# Z-ONE.net
KiCad netlist of a schematic drawn in EAGLE
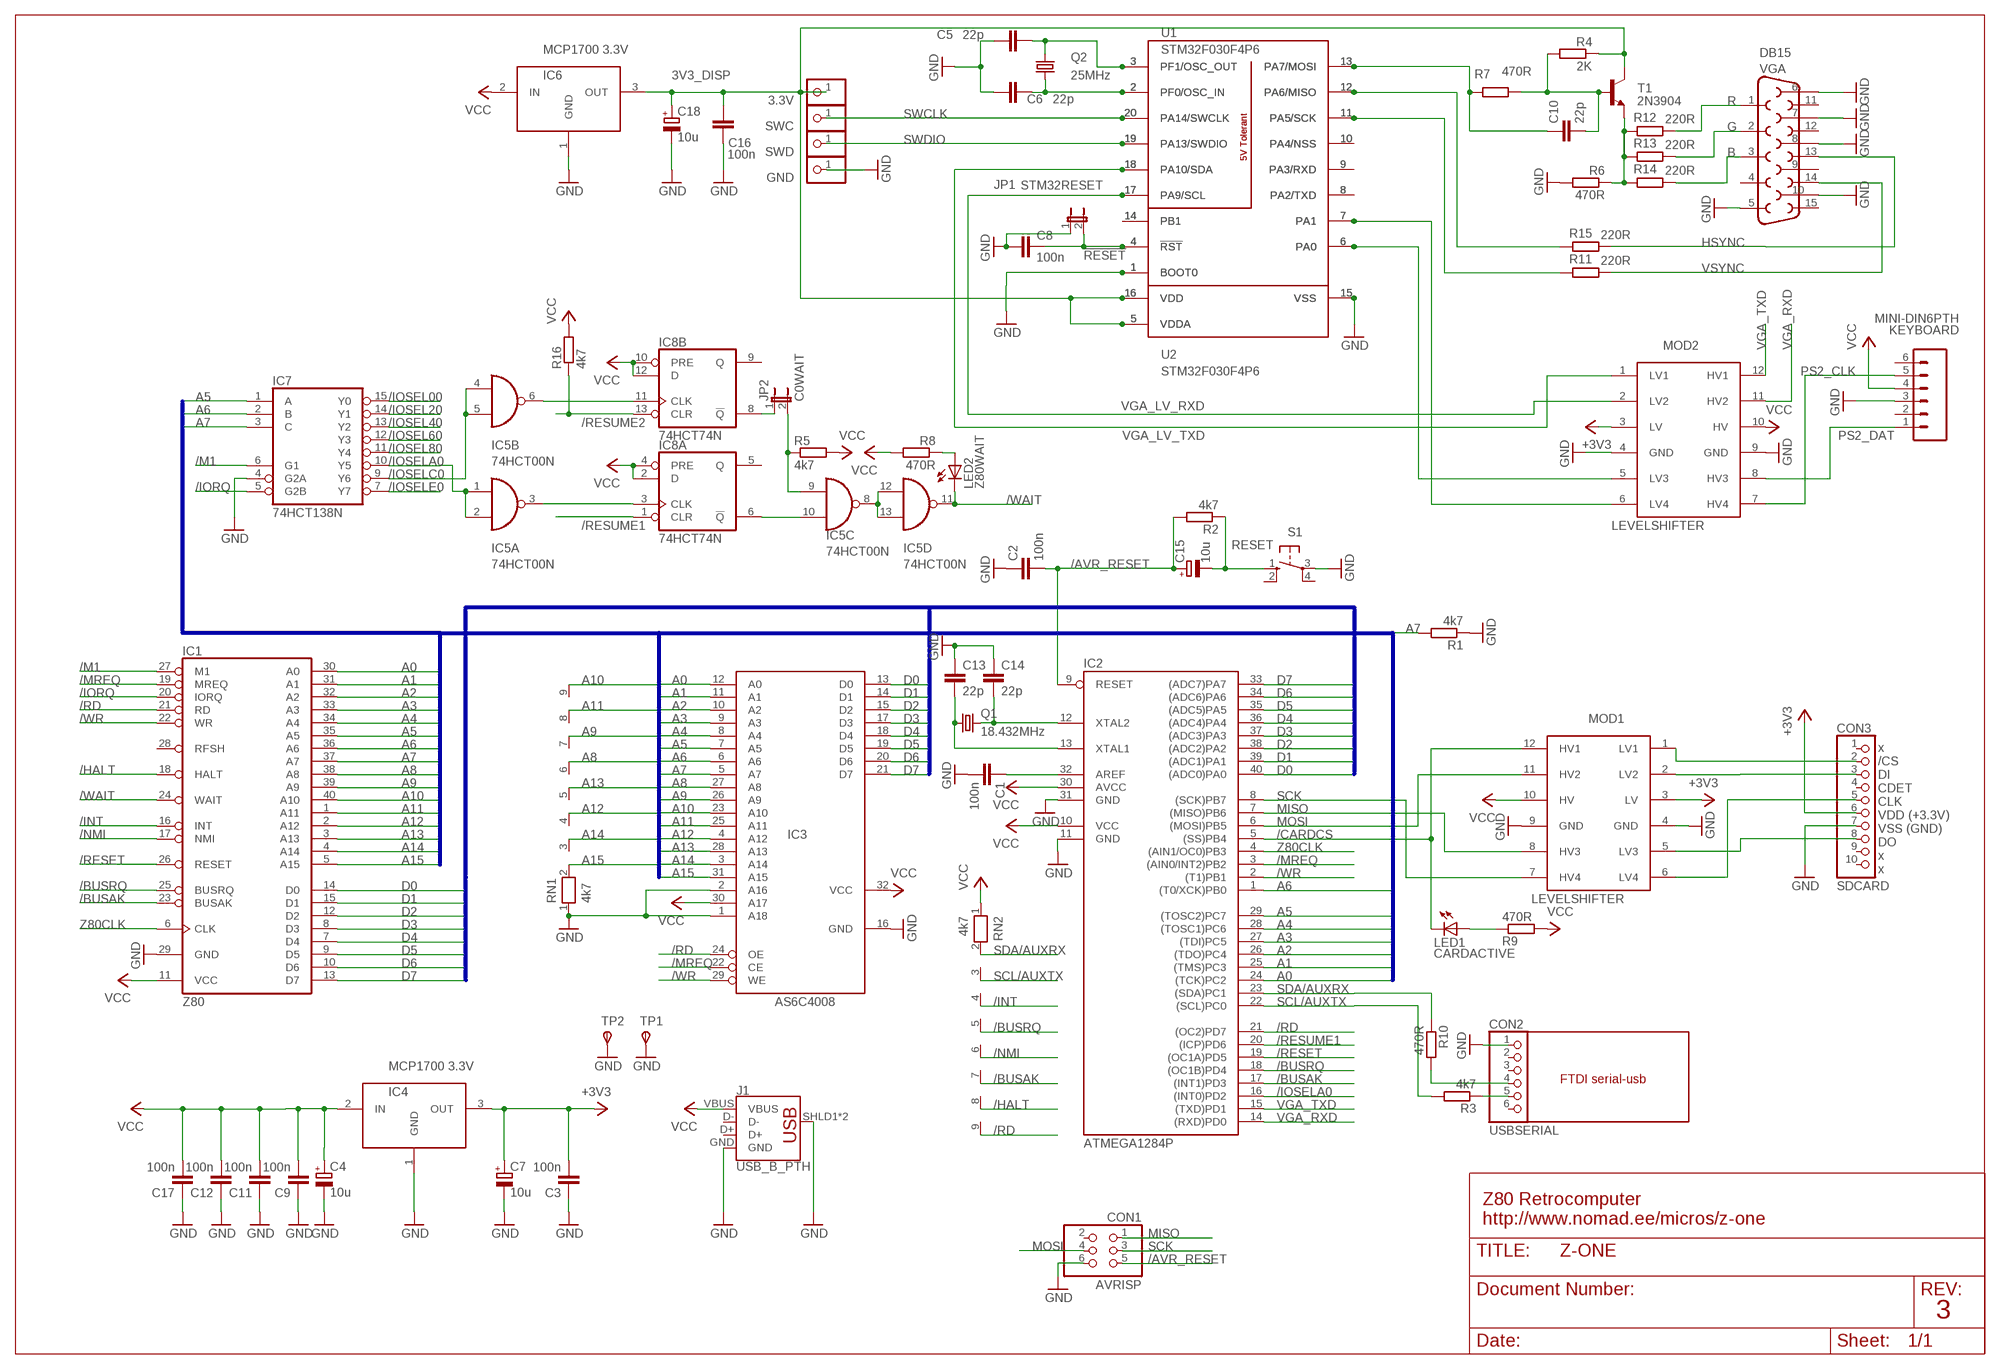
[diagram p0: schematic, sheet 1]

(export (version "E")
  (design (tool "Eeschema 10.0.6"))
  (components
    (comp (ref "3.3V")
      (value "PINHD-1X1")
      (footprint "eagle-import:1X01")
      (libsource (lib "eagle-import") (part "PINHD-1X1"))
    )
    (comp (ref "C1")
      (value "100n")
      (footprint "eagle-import:C025-025X050")
      (fields (field (name "PARTNO") "0.1UF, 0603"))
      (libsource (lib "eagle-import") (part "C-EU025-025X050"))
    )
    (comp (ref "C2")
      (value "100n")
      (footprint "eagle-import:C025-025X050")
      (fields (field (name "PARTNO") "0.1UF, 0603"))
      (libsource (lib "eagle-import") (part "C-EU025-025X050"))
    )
    (comp (ref "C3")
      (value "100n")
      (footprint "eagle-import:C025-025X050")
      (fields (field (name "PARTNO") "0.1UF, 0603"))
      (libsource (lib "eagle-import") (part "C-EU025-025X050"))
    )
    (comp (ref "C4")
      (value "10u")
      (footprint "eagle-import:E2,5-5")
      (libsource (lib "eagle-import") (part "CPOL-EUE2.5-5"))
    )
    (comp (ref "C5")
      (value "22p")
      (footprint "eagle-import:C025-025X050")
      (fields (field (name "PARTNO") "22PF, 0603"))
      (libsource (lib "eagle-import") (part "C-EU025-025X050"))
    )
    (comp (ref "C6")
      (value "22p")
      (footprint "eagle-import:C025-025X050")
      (fields (field (name "PARTNO") "22PF, 0603"))
      (libsource (lib "eagle-import") (part "C-EU025-025X050"))
    )
    (comp (ref "C7")
      (value "10u")
      (footprint "eagle-import:E2,5-5")
      (libsource (lib "eagle-import") (part "CPOL-EUE2.5-5"))
    )
    (comp (ref "C8")
      (value "100n")
      (footprint "eagle-import:C025-025X050")
      (fields (field (name "PARTNO") "0.1UF, 0603"))
      (libsource (lib "eagle-import") (part "C-EU025-025X050"))
    )
    (comp (ref "C9")
      (value "100n")
      (footprint "eagle-import:C025-025X050")
      (fields (field (name "PARTNO") "0.1UF, 0603"))
      (libsource (lib "eagle-import") (part "C-EU025-025X050"))
    )
    (comp (ref "C10")
      (value "22p")
      (footprint "eagle-import:C025-025X050")
      (fields (field (name "PARTNO") "22PF, 0603"))
      (libsource (lib "eagle-import") (part "C-EU025-025X050"))
    )
    (comp (ref "C11")
      (value "100n")
      (footprint "eagle-import:C025-025X050")
      (fields (field (name "PARTNO") "0.1UF, 0603"))
      (libsource (lib "eagle-import") (part "C-EU025-025X050"))
    )
    (comp (ref "C12")
      (value "100n")
      (footprint "eagle-import:C025-025X050")
      (fields (field (name "PARTNO") "0.1UF, 0603"))
      (libsource (lib "eagle-import") (part "C-EU025-025X050"))
    )
    (comp (ref "C13")
      (value "22p")
      (footprint "eagle-import:C025-025X050")
      (fields (field (name "PARTNO") "0.1UF, 0603"))
      (libsource (lib "eagle-import") (part "C-EU025-025X050"))
    )
    (comp (ref "C14")
      (value "22p")
      (footprint "eagle-import:C025-025X050")
      (fields (field (name "PARTNO") "0.1UF, 0603"))
      (libsource (lib "eagle-import") (part "C-EU025-025X050"))
    )
    (comp (ref "C15")
      (value "10u")
      (footprint "eagle-import:E2,5-5")
      (libsource (lib "eagle-import") (part "CPOL-EUE2.5-5"))
    )
    (comp (ref "C16")
      (value "100n")
      (footprint "eagle-import:C025-025X050")
      (fields (field (name "PARTNO") "0.1UF, 0603"))
      (libsource (lib "eagle-import") (part "C-EU025-025X050"))
    )
    (comp (ref "C17")
      (value "100n")
      (footprint "eagle-import:C025-025X050")
      (fields (field (name "PARTNO") "0.1UF, 0603"))
      (libsource (lib "eagle-import") (part "C-EU025-025X050"))
    )
    (comp (ref "C18")
      (value "10u")
      (footprint "eagle-import:E2,5-5")
      (libsource (lib "eagle-import") (part "CPOL-EUE2.5-5"))
    )
    (comp (ref "CON1")
      (value "AVRISP")
      (footprint "eagle-import:2X03")
      (libsource (lib "eagle-import") (part "PINHD-2X3"))
    )
    (comp (ref "CON2")
      (value "USBSERIAL")
      (footprint "eagle-import:1X06")
      (libsource (lib "eagle-import") (part "PINHD-1X6"))
    )
    (comp (ref "CON3")
      (value "SDCARD")
      (footprint "eagle-import:1X10")
      (libsource (lib "eagle-import") (part "PINHD-1X10"))
    )
    (comp (ref "GND")
      (value "PINHD-1X1")
      (footprint "eagle-import:1X01")
      (libsource (lib "eagle-import") (part "PINHD-1X1"))
    )
    (comp (ref "IC1")
      (value "Z80")
      (footprint "eagle-import:DIL40")
      (libsource (lib "eagle-import") (part "Z80CPU"))
    )
    (comp (ref "IC2")
      (value "ATMEGA1284P")
      (footprint "eagle-import:DIL40")
      (fields (field (name "MPN") "ATMEGA32-16PU"))
      (libsource (lib "eagle-import") (part "MEGA32-P"))
    )
    (comp (ref "IC3")
      (value "AS6C4008")
      (footprint "eagle-import:DIP32")
      (libsource (lib "eagle-import") (part "AS6C4008DIP32"))
    )
    (comp (ref "IC4")
      (value "MCP1700 3.3V")
      (footprint "eagle-import:TO-92")
      (libsource (lib "eagle-import") (part "MCP1700TO92"))
    )
    (comp (ref "IC5")
      (value "74HCT00N")
      (footprint "eagle-import:DIL14")
      (libsource (lib "eagle-import") (part "7400NHCT"))
    )
    (comp (ref "IC6")
      (value "MCP1700 3.3V")
      (footprint "eagle-import:TO-92")
      (libsource (lib "eagle-import") (part "MCP1700TO92"))
    )
    (comp (ref "IC7")
      (value "74HCT138N")
      (footprint "eagle-import:DIL16")
      (libsource (lib "eagle-import") (part "74138NHCT"))
    )
    (comp (ref "IC8")
      (value "74HCT74N")
      (footprint "eagle-import:DIL14")
      (libsource (lib "eagle-import") (part "7474NHCT"))
    )
    (comp (ref "J1")
      (value "USB_B_PTH")
      (footprint "eagle-import:USB-B-PTH")
      (libsource (lib "eagle-import") (part "USB_B_PTH"))
    )
    (comp (ref "JP1")
      (value "STM32RESET")
      (footprint "eagle-import:1X02")
      (libsource (lib "eagle-import") (part "JUMPER-2PTH"))
    )
    (comp (ref "JP2")
      (value "C0WAIT")
      (footprint "eagle-import:1X02")
      (libsource (lib "eagle-import") (part "JUMPER-2PTH"))
    )
    (comp (ref "KEYBOARD")
      (value "MINI-DIN6PTH")
      (footprint "eagle-import:MINI-DIN6")
      (libsource (lib "eagle-import") (part "MINI-DIN6PTH"))
    )
    (comp (ref "LED1")
      (value "CARDACTIVE")
      (footprint "eagle-import:LED3MM")
      (libsource (lib "eagle-import") (part "LED3MM"))
    )
    (comp (ref "LED2")
      (value "Z80WAIT")
      (footprint "eagle-import:LED3MM")
      (libsource (lib "eagle-import") (part "LED3MM"))
    )
    (comp (ref "MOD1")
      (value "LEVELSHIFTER")
      (footprint "eagle-import:LAVELSHIFTER_N")
      (libsource (lib "eagle-import") (part "LEVELSHIFTERNARROW"))
    )
    (comp (ref "MOD2")
      (value "LEVELSHIFTER")
      (footprint "eagle-import:LAVELSHIFTER_N")
      (libsource (lib "eagle-import") (part "LEVELSHIFTERNARROW"))
    )
    (comp (ref "Q1")
      (value "18.432MHz")
      (footprint "eagle-import:HC49_S")
      (libsource (lib "eagle-import") (part "CRYSTALHC49S"))
    )
    (comp (ref "Q2")
      (value "25MHz")
      (footprint "eagle-import:HC49_S")
      (libsource (lib "eagle-import") (part "CRYSTALHC49S"))
    )
    (comp (ref "R1")
      (value "4k7")
      (footprint "eagle-import:0204_7")
      (libsource (lib "eagle-import") (part "R-EU_0204/7"))
    )
    (comp (ref "R2")
      (value "4k7")
      (footprint "eagle-import:0204_7")
      (libsource (lib "eagle-import") (part "R-EU_0204/7"))
    )
    (comp (ref "R3")
      (value "4k7")
      (footprint "eagle-import:0204_7")
      (libsource (lib "eagle-import") (part "R-EU_0204/7"))
    )
    (comp (ref "R4")
      (value "2K")
      (footprint "eagle-import:0204_7")
      (fields (field (name "PARTNO") "2K, 0603"))
      (libsource (lib "eagle-import") (part "resistor_R-EU_0204/7"))
    )
    (comp (ref "R5")
      (value "4k7")
      (footprint "eagle-import:0204_7")
      (libsource (lib "eagle-import") (part "R-EU_0204/7"))
    )
    (comp (ref "R6")
      (value "470R")
      (footprint "eagle-import:0204_7")
      (fields (field (name "PARTNO") "475R, 0603"))
      (libsource (lib "eagle-import") (part "resistor_R-EU_0204/7"))
    )
    (comp (ref "R7")
      (value "470R")
      (footprint "eagle-import:0204_7")
      (fields (field (name "PARTNO") "475R, 0603"))
      (libsource (lib "eagle-import") (part "resistor_R-EU_0204/7"))
    )
    (comp (ref "R8")
      (value "470R")
      (footprint "eagle-import:0204_7")
      (fields (field (name "PARTNO") "475R, 0603"))
      (libsource (lib "eagle-import") (part "resistor_R-EU_0204/7"))
    )
    (comp (ref "R9")
      (value "470R")
      (footprint "eagle-import:0204_7")
      (fields (field (name "PARTNO") "475R, 0603"))
      (libsource (lib "eagle-import") (part "resistor_R-EU_0204/7"))
    )
    (comp (ref "R10")
      (value "470R")
      (footprint "eagle-import:0204_7")
      (libsource (lib "eagle-import") (part "R-EU_0204/7"))
    )
    (comp (ref "R11")
      (value "220R")
      (footprint "eagle-import:0204_7")
      (libsource (lib "eagle-import") (part "resistor_R-EU_0204/7"))
    )
    (comp (ref "R12")
      (value "220R")
      (footprint "eagle-import:0204_7")
      (libsource (lib "eagle-import") (part "resistor_R-EU_0204/7"))
    )
    (comp (ref "R13")
      (value "220R")
      (footprint "eagle-import:0204_7")
      (libsource (lib "eagle-import") (part "resistor_R-EU_0204/7"))
    )
    (comp (ref "R14")
      (value "220R")
      (footprint "eagle-import:0204_7")
      (libsource (lib "eagle-import") (part "resistor_R-EU_0204/7"))
    )
    (comp (ref "R15")
      (value "220R")
      (footprint "eagle-import:0204_7")
      (libsource (lib "eagle-import") (part "resistor_R-EU_0204/7"))
    )
    (comp (ref "R16")
      (value "4k7")
      (footprint "eagle-import:0204_7")
      (libsource (lib "eagle-import") (part "R-EU_0204/7"))
    )
    (comp (ref "RN1")
      (value "4k7")
      (footprint "eagle-import:RN-9")
      (libsource (lib "eagle-import") (part "RN08"))
    )
    (comp (ref "RN2")
      (value "4k7")
      (footprint "eagle-import:RN-9")
      (libsource (lib "eagle-import") (part "RN08"))
    )
    (comp (ref "S1")
      (value "RESET")
      (footprint "eagle-import:B3F-10XX")
      (fields (field (name "MPN") "B3F-1000"))
      (libsource (lib "eagle-import") (part "10-XX"))
    )
    (comp (ref "SWC")
      (value "PINHD-1X1")
      (footprint "eagle-import:1X01")
      (libsource (lib "eagle-import") (part "PINHD-1X1"))
    )
    (comp (ref "SWD")
      (value "PINHD-1X1")
      (footprint "eagle-import:1X01")
      (libsource (lib "eagle-import") (part "PINHD-1X1"))
    )
    (comp (ref "T1")
      (value "2N3904")
      (footprint "eagle-import:TO92")
      (libsource (lib "eagle-import") (part "2N3904"))
    )
    (comp (ref "TP1")
      (value "GND")
      (footprint "eagle-import:P1-13")
      (libsource (lib "eagle-import") (part "TPSPAD1-13"))
    )
    (comp (ref "TP2")
      (value "GND")
      (footprint "eagle-import:P1-13")
      (libsource (lib "eagle-import") (part "TPSPAD1-13"))
    )
    (comp (ref "U1")
      (value "STM32F030F4P6")
      (footprint "eagle-import:DIL20WIDE")
      (libsource (lib "eagle-import") (part "MISC-PROCESSOR_STM32F030F4P6DIL20MODULE"))
    )
    (comp (ref "U2")
      (value "STM32F030F4P6")
      (footprint "eagle-import:MISC-PROCESSOR_TSSOP20")
      (libsource (lib "eagle-import") (part "MISC-PROCESSOR_STM32F030F4P6"))
    )
    (comp (ref "VGA")
      (value "DB15")
      (footprint "eagle-import:DB15")
      (libsource (lib "eagle-import") (part "DB15"))
    )
  )
  (nets
    (net (code "1") (name "+3V3") (class "Default")
      (node (ref "C3") (pin "2") (pinfunction "2_2") (pintype "passive"))
      (node (ref "C7") (pin "+") (pinfunction "+_+") (pintype "passive"))
      (node (ref "CON3") (pin "6") (pinfunction "6_6") (pintype "passive"))
      (node (ref "IC4") (pin "3") (pinfunction "OUT_3") (pintype "bidirectional"))
      (node (ref "MOD1") (pin "3") (pinfunction "LV_3") (pintype "bidirectional"))
      (node (ref "MOD2") (pin "3") (pinfunction "LV_3") (pintype "bidirectional"))
    )
    (net (code "2") (name "/3V3_DISP") (class "Default")
      (node (ref "3.3V") (pin "1") (pinfunction "1_1") (pintype "passive"))
      (node (ref "C16") (pin "1") (pinfunction "1_1") (pintype "passive"))
      (node (ref "C18") (pin "+") (pinfunction "+_+") (pintype "passive"))
      (node (ref "IC6") (pin "3") (pinfunction "OUT_3") (pintype "bidirectional"))
      (node (ref "R4") (pin "1") (pinfunction "1_1") (pintype "passive"))
      (node (ref "T1") (pin "1") (pinfunction "C_1") (pintype "passive"))
      (node (ref "U1") (pin "16") (pinfunction "VDD_16") (pintype "input"))
      (node (ref "U1") (pin "5") (pinfunction "VDDA_5") (pintype "input"))
      (node (ref "U2") (pin "16") (pinfunction "VDD_16") (pintype "input"))
      (node (ref "U2") (pin "5") (pinfunction "VDDA_5") (pintype "input"))
    )
    (net (code "3") (name "/A0") (class "Default")
      (node (ref "IC1") (pin "30") (pinfunction "A0_30") (pintype "output"))
      (node (ref "IC2") (pin "24") (pinfunction "(TCK)PC2_24") (pintype "bidirectional"))
      (node (ref "IC3") (pin "12") (pinfunction "A0_12") (pintype "input"))
    )
    (net (code "4") (name "/A1") (class "Default")
      (node (ref "IC1") (pin "31") (pinfunction "A1_31") (pintype "output"))
      (node (ref "IC2") (pin "25") (pinfunction "(TMS)PC3_25") (pintype "bidirectional"))
      (node (ref "IC3") (pin "11") (pinfunction "A1_11") (pintype "input"))
    )
    (net (code "5") (name "/A2") (class "Default")
      (node (ref "IC1") (pin "32") (pinfunction "A2_32") (pintype "output"))
      (node (ref "IC2") (pin "26") (pinfunction "(TDO)PC4_26") (pintype "bidirectional"))
      (node (ref "IC3") (pin "10") (pinfunction "A2_10") (pintype "input"))
    )
    (net (code "6") (name "/A3") (class "Default")
      (node (ref "IC1") (pin "33") (pinfunction "A3_33") (pintype "output"))
      (node (ref "IC2") (pin "27") (pinfunction "(TDI)PC5_27") (pintype "bidirectional"))
      (node (ref "IC3") (pin "9") (pinfunction "A3_9") (pintype "input"))
    )
    (net (code "7") (name "/A4") (class "Default")
      (node (ref "IC1") (pin "34") (pinfunction "A4_34") (pintype "output"))
      (node (ref "IC2") (pin "28") (pinfunction "(TOSC1)PC6_28") (pintype "bidirectional"))
      (node (ref "IC3") (pin "8") (pinfunction "A4_8") (pintype "input"))
    )
    (net (code "8") (name "/A5") (class "Default")
      (node (ref "IC1") (pin "35") (pinfunction "A5_35") (pintype "output"))
      (node (ref "IC2") (pin "29") (pinfunction "(TOSC2)PC7_29") (pintype "bidirectional"))
      (node (ref "IC3") (pin "7") (pinfunction "A5_7") (pintype "input"))
      (node (ref "IC7") (pin "1") (pinfunction "A_1") (pintype "input"))
    )
    (net (code "9") (name "/A6") (class "Default")
      (node (ref "IC1") (pin "36") (pinfunction "A6_36") (pintype "output"))
      (node (ref "IC2") (pin "1") (pinfunction "(T0/XCK)PB0_1") (pintype "bidirectional"))
      (node (ref "IC3") (pin "6") (pinfunction "A6_6") (pintype "input"))
      (node (ref "IC7") (pin "2") (pinfunction "B_2") (pintype "input"))
    )
    (net (code "10") (name "/A7") (class "Default")
      (node (ref "IC1") (pin "37") (pinfunction "A7_37") (pintype "output"))
      (node (ref "IC3") (pin "5") (pinfunction "A7_5") (pintype "input"))
      (node (ref "IC7") (pin "3") (pinfunction "C_3") (pintype "input"))
      (node (ref "R1") (pin "2") (pinfunction "2_2") (pintype "passive"))
    )
    (net (code "11") (name "/A8") (class "Default")
      (node (ref "IC1") (pin "38") (pinfunction "A8_38") (pintype "output"))
      (node (ref "IC3") (pin "27") (pinfunction "A8_27") (pintype "input"))
      (node (ref "RN1") (pin "6") (pinfunction "6_6") (pintype "passive"))
    )
    (net (code "12") (name "/A9") (class "Default")
      (node (ref "IC1") (pin "39") (pinfunction "A9_39") (pintype "output"))
      (node (ref "IC3") (pin "26") (pinfunction "A9_26") (pintype "input"))
      (node (ref "RN1") (pin "7") (pinfunction "7_7") (pintype "passive"))
    )
    (net (code "13") (name "/A10") (class "Default")
      (node (ref "IC1") (pin "40") (pinfunction "A10_40") (pintype "output"))
      (node (ref "IC3") (pin "23") (pinfunction "A10_23") (pintype "input"))
      (node (ref "RN1") (pin "9") (pinfunction "9_9") (pintype "passive"))
    )
    (net (code "14") (name "/A11") (class "Default")
      (node (ref "IC1") (pin "1") (pinfunction "A11_1") (pintype "output"))
      (node (ref "IC3") (pin "25") (pinfunction "A11_25") (pintype "input"))
      (node (ref "RN1") (pin "8") (pinfunction "8_8") (pintype "passive"))
    )
    (net (code "15") (name "/A12") (class "Default")
      (node (ref "IC1") (pin "2") (pinfunction "A12_2") (pintype "output"))
      (node (ref "IC3") (pin "4") (pinfunction "A12_4") (pintype "input"))
      (node (ref "RN1") (pin "4") (pinfunction "4_4") (pintype "passive"))
    )
    (net (code "16") (name "/A13") (class "Default")
      (node (ref "IC1") (pin "3") (pinfunction "A13_3") (pintype "output"))
      (node (ref "IC3") (pin "28") (pinfunction "A13_28") (pintype "input"))
      (node (ref "RN1") (pin "5") (pinfunction "5_5") (pintype "passive"))
    )
    (net (code "17") (name "/A14") (class "Default")
      (node (ref "IC1") (pin "4") (pinfunction "A14_4") (pintype "output"))
      (node (ref "IC3") (pin "3") (pinfunction "A14_3") (pintype "input"))
      (node (ref "RN1") (pin "3") (pinfunction "3_3") (pintype "passive"))
    )
    (net (code "18") (name "/A15") (class "Default")
      (node (ref "IC1") (pin "5") (pinfunction "A15_5") (pintype "output"))
      (node (ref "IC3") (pin "31") (pinfunction "A15_31") (pintype "input"))
      (node (ref "RN1") (pin "2") (pinfunction "2_2") (pintype "passive"))
    )
    (net (code "19") (name "/B") (class "Default")
      (node (ref "R14") (pin "1") (pinfunction "1_1") (pintype "passive"))
      (node (ref "VGA") (pin "3") (pinfunction "3_3") (pintype "passive"))
    )
    (net (code "20") (name "/D0") (class "Default")
      (node (ref "IC1") (pin "14") (pinfunction "D0_14") (pintype "bidirectional"))
      (node (ref "IC2") (pin "40") (pinfunction "(ADC0)PA0_40") (pintype "bidirectional"))
      (node (ref "IC3") (pin "13") (pinfunction "D0_13") (pintype "bidirectional"))
    )
    (net (code "21") (name "/D1") (class "Default")
      (node (ref "IC1") (pin "15") (pinfunction "D1_15") (pintype "bidirectional"))
      (node (ref "IC2") (pin "39") (pinfunction "(ADC1)PA1_39") (pintype "bidirectional"))
      (node (ref "IC3") (pin "14") (pinfunction "D1_14") (pintype "bidirectional"))
    )
    (net (code "22") (name "/D2") (class "Default")
      (node (ref "IC1") (pin "12") (pinfunction "D2_12") (pintype "bidirectional"))
      (node (ref "IC2") (pin "38") (pinfunction "(ADC2)PA2_38") (pintype "bidirectional"))
      (node (ref "IC3") (pin "15") (pinfunction "D2_15") (pintype "bidirectional"))
    )
    (net (code "23") (name "/D3") (class "Default")
      (node (ref "IC1") (pin "8") (pinfunction "D3_8") (pintype "bidirectional"))
      (node (ref "IC2") (pin "37") (pinfunction "(ADC3)PA3_37") (pintype "bidirectional"))
      (node (ref "IC3") (pin "17") (pinfunction "D3_17") (pintype "bidirectional"))
    )
    (net (code "24") (name "/D4") (class "Default")
      (node (ref "IC1") (pin "7") (pinfunction "D4_7") (pintype "bidirectional"))
      (node (ref "IC2") (pin "36") (pinfunction "(ADC4)PA4_36") (pintype "bidirectional"))
      (node (ref "IC3") (pin "18") (pinfunction "D4_18") (pintype "bidirectional"))
    )
    (net (code "25") (name "/D5") (class "Default")
      (node (ref "IC1") (pin "9") (pinfunction "D5_9") (pintype "bidirectional"))
      (node (ref "IC2") (pin "35") (pinfunction "(ADC5)PA5_35") (pintype "bidirectional"))
      (node (ref "IC3") (pin "19") (pinfunction "D5_19") (pintype "bidirectional"))
    )
    (net (code "26") (name "/D6") (class "Default")
      (node (ref "IC1") (pin "10") (pinfunction "D6_10") (pintype "bidirectional"))
      (node (ref "IC2") (pin "34") (pinfunction "(ADC6)PA6_34") (pintype "bidirectional"))
      (node (ref "IC3") (pin "20") (pinfunction "D6_20") (pintype "bidirectional"))
    )
    (net (code "27") (name "/D7") (class "Default")
      (node (ref "IC1") (pin "13") (pinfunction "D7_13") (pintype "bidirectional"))
      (node (ref "IC2") (pin "33") (pinfunction "(ADC7)PA7_33") (pintype "bidirectional"))
      (node (ref "IC3") (pin "21") (pinfunction "D7_21") (pintype "bidirectional"))
    )
    (net (code "28") (name "/G") (class "Default")
      (node (ref "R13") (pin "1") (pinfunction "1_1") (pintype "passive"))
      (node (ref "VGA") (pin "2") (pinfunction "2_2") (pintype "passive"))
    )
    (net (code "29") (name "/HSYNC") (class "Default")
      (node (ref "R15") (pin "1") (pinfunction "1_1") (pintype "passive"))
      (node (ref "VGA") (pin "13") (pinfunction "13_13") (pintype "passive"))
    )
    (net (code "30") (name "/MISO") (class "Default")
      (node (ref "CON1") (pin "1") (pinfunction "1_1") (pintype "passive"))
      (node (ref "IC2") (pin "7") (pinfunction "(MISO)PB6_7") (pintype "bidirectional"))
      (node (ref "MOD1") (pin "8") (pinfunction "HV3_8") (pintype "bidirectional"))
    )
    (net (code "31") (name "/MOSI") (class "Default")
      (node (ref "CON1") (pin "4") (pinfunction "4_4") (pintype "passive"))
      (node (ref "IC2") (pin "6") (pinfunction "(MOSI)PB5_6") (pintype "bidirectional"))
      (node (ref "MOD1") (pin "11") (pinfunction "HV2_11") (pintype "bidirectional"))
    )
    (net (code "32") (name "/PS2_CLK") (class "Default")
      (node (ref "KEYBOARD") (pin "5") (pinfunction "5_5") (pintype "passive"))
      (node (ref "MOD2") (pin "7") (pinfunction "HV4_7") (pintype "bidirectional"))
    )
    (net (code "33") (name "/PS2_DAT") (class "Default")
      (node (ref "KEYBOARD") (pin "1") (pinfunction "1_1") (pintype "passive"))
      (node (ref "MOD2") (pin "8") (pinfunction "HV3_8") (pintype "bidirectional"))
    )
    (net (code "34") (name "/R") (class "Default")
      (node (ref "R12") (pin "1") (pinfunction "1_1") (pintype "passive"))
      (node (ref "VGA") (pin "1") (pinfunction "1_1") (pintype "passive"))
    )
    (net (code "35") (name "/SCK") (class "Default")
      (node (ref "CON1") (pin "3") (pinfunction "3_3") (pintype "passive"))
      (node (ref "IC2") (pin "8") (pinfunction "(SCK)PB7_8") (pintype "bidirectional"))
      (node (ref "MOD1") (pin "7") (pinfunction "HV4_7") (pintype "bidirectional"))
    )
    (net (code "36") (name "/SCL{slash}AUXTX") (class "Default")
      (node (ref "IC2") (pin "22") (pinfunction "(SCL)PC0_22") (pintype "bidirectional"))
      (node (ref "R3") (pin "2") (pinfunction "2_2") (pintype "passive"))
      (node (ref "RN2") (pin "3") (pinfunction "3_3") (pintype "passive"))
    )
    (net (code "37") (name "/SDA{slash}AUXRX") (class "Default")
      (node (ref "IC2") (pin "23") (pinfunction "(SDA)PC1_23") (pintype "bidirectional"))
      (node (ref "R10") (pin "1") (pinfunction "1_1") (pintype "passive"))
      (node (ref "RN2") (pin "2") (pinfunction "2_2") (pintype "passive"))
    )
    (net (code "38") (name "/SWCLK") (class "Default")
      (node (ref "SWC") (pin "1") (pinfunction "1_1") (pintype "passive"))
      (node (ref "U1") (pin "20") (pinfunction "PA14/SWCLK_20") (pintype "bidirectional"))
      (node (ref "U2") (pin "20") (pinfunction "PA14/SWCLK_20") (pintype "bidirectional"))
    )
    (net (code "39") (name "/SWDIO") (class "Default")
      (node (ref "SWD") (pin "1") (pinfunction "1_1") (pintype "passive"))
      (node (ref "U1") (pin "19") (pinfunction "PA13/SWDIO_19") (pintype "bidirectional"))
      (node (ref "U2") (pin "19") (pinfunction "PA13/SWDIO_19") (pintype "bidirectional"))
    )
    (net (code "40") (name "/VGA_LV_RXD") (class "Default")
      (node (ref "MOD2") (pin "2") (pinfunction "LV2_2") (pintype "bidirectional"))
      (node (ref "U1") (pin "17") (pinfunction "PA9/SCL_17") (pintype "bidirectional"))
      (node (ref "U2") (pin "17") (pinfunction "PA9/SCL_17") (pintype "bidirectional"))
    )
    (net (code "41") (name "/VGA_LV_TXD") (class "Default")
      (node (ref "MOD2") (pin "1") (pinfunction "LV1_1") (pintype "bidirectional"))
      (node (ref "U1") (pin "18") (pinfunction "PA10/SDA_18") (pintype "bidirectional"))
      (node (ref "U2") (pin "18") (pinfunction "PA10/SDA_18") (pintype "bidirectional"))
    )
    (net (code "42") (name "/VGA_RXD") (class "Default")
      (node (ref "IC2") (pin "14") (pinfunction "(RXD)PD0_14") (pintype "bidirectional"))
      (node (ref "MOD2") (pin "11") (pinfunction "HV2_11") (pintype "bidirectional"))
    )
    (net (code "43") (name "/VGA_TXD") (class "Default")
      (node (ref "IC2") (pin "15") (pinfunction "(TXD)PD1_15") (pintype "bidirectional"))
      (node (ref "MOD2") (pin "12") (pinfunction "HV1_12") (pintype "bidirectional"))
    )
    (net (code "44") (name "/VSYNC") (class "Default")
      (node (ref "R11") (pin "1") (pinfunction "1_1") (pintype "passive"))
      (node (ref "VGA") (pin "14") (pinfunction "14_14") (pintype "passive"))
    )
    (net (code "45") (name "/Z80CLK") (class "Default")
      (node (ref "IC1") (pin "6") (pinfunction "CLK_6") (pintype "input"))
      (node (ref "IC2") (pin "4") (pinfunction "(AIN1/OC0)PB3_4") (pintype "bidirectional"))
    )
    (net (code "46") (name "/{slash}AVR_RESET") (class "Default")
      (node (ref "C15") (pin "+") (pinfunction "+_+") (pintype "passive"))
      (node (ref "C2") (pin "2") (pinfunction "2_2") (pintype "passive"))
      (node (ref "CON1") (pin "5") (pinfunction "5_5") (pintype "passive"))
      (node (ref "IC2") (pin "9") (pinfunction "RESET_9") (pintype "input"))
      (node (ref "R2") (pin "2") (pinfunction "2_2") (pintype "passive"))
    )
    (net (code "47") (name "/{slash}BUSAK") (class "Default")
      (node (ref "IC1") (pin "23") (pinfunction "BUSAK_23") (pintype "output"))
      (node (ref "IC2") (pin "17") (pinfunction "(INT1)PD3_17") (pintype "bidirectional"))
      (node (ref "RN2") (pin "7") (pinfunction "7_7") (pintype "passive"))
    )
    (net (code "48") (name "/{slash}BUSRQ") (class "Default")
      (node (ref "IC1") (pin "25") (pinfunction "BUSRQ_25") (pintype "input"))
      (node (ref "IC2") (pin "18") (pinfunction "(OC1B)PD4_18") (pintype "bidirectional"))
      (node (ref "RN2") (pin "5") (pinfunction "5_5") (pintype "passive"))
    )
    (net (code "49") (name "/{slash}CARDCS") (class "Default")
      (node (ref "IC2") (pin "5") (pinfunction "(SS)PB4_5") (pintype "bidirectional"))
      (node (ref "LED1") (pin "K") (pinfunction "C_K") (pintype "passive"))
      (node (ref "MOD1") (pin "12") (pinfunction "HV1_12") (pintype "bidirectional"))
    )
    (net (code "50") (name "/{slash}HALT") (class "Default")
      (node (ref "IC1") (pin "18") (pinfunction "HALT_18") (pintype "output"))
      (node (ref "RN2") (pin "8") (pinfunction "8_8") (pintype "passive"))
    )
    (net (code "51") (name "/{slash}INT") (class "Default")
      (node (ref "IC1") (pin "16") (pinfunction "INT_16") (pintype "input"))
      (node (ref "RN2") (pin "4") (pinfunction "4_4") (pintype "passive"))
    )
    (net (code "52") (name "/{slash}IORQ") (class "Default")
      (node (ref "IC1") (pin "20") (pinfunction "IORQ_20") (pintype "output"))
      (node (ref "IC7") (pin "5") (pinfunction "G2B_5") (pintype "input"))
    )
    (net (code "53") (name "/{slash}IOSEL00") (class "Default")
      (node (ref "IC7") (pin "15") (pinfunction "Y0_15") (pintype "output"))
    )
    (net (code "54") (name "/{slash}IOSEL20") (class "Default")
      (node (ref "IC7") (pin "14") (pinfunction "Y1_14") (pintype "output"))
    )
    (net (code "55") (name "/{slash}IOSEL40") (class "Default")
      (node (ref "IC7") (pin "13") (pinfunction "Y2_13") (pintype "output"))
    )
    (net (code "56") (name "/{slash}IOSEL60") (class "Default")
      (node (ref "IC7") (pin "12") (pinfunction "Y3_12") (pintype "output"))
    )
    (net (code "57") (name "/{slash}IOSEL80") (class "Default")
      (node (ref "IC7") (pin "11") (pinfunction "Y4_11") (pintype "output"))
    )
    (net (code "58") (name "/{slash}IOSELA0") (class "Default")
      (node (ref "IC2") (pin "16") (pinfunction "(INT0)PD2_16") (pintype "bidirectional"))
      (node (ref "IC5") (pin "1") (pinfunction "I0_1") (pintype "input"))
      (node (ref "IC5") (pin "2") (pinfunction "I1_2") (pintype "input"))
      (node (ref "IC7") (pin "10") (pinfunction "Y5_10") (pintype "output"))
    )
    (net (code "59") (name "/{slash}IOSELC0") (class "Default")
      (node (ref "IC5") (pin "4") (pinfunction "I0_4") (pintype "input"))
      (node (ref "IC5") (pin "5") (pinfunction "I1_5") (pintype "input"))
      (node (ref "IC7") (pin "9") (pinfunction "Y6_9") (pintype "output"))
    )
    (net (code "60") (name "/{slash}IOSELE0") (class "Default")
      (node (ref "IC7") (pin "7") (pinfunction "Y7_7") (pintype "output"))
    )
    (net (code "61") (name "/{slash}M1") (class "Default")
      (node (ref "IC1") (pin "27") (pinfunction "M1_27") (pintype "output"))
      (node (ref "IC7") (pin "6") (pinfunction "G1_6") (pintype "input"))
    )
    (net (code "62") (name "/{slash}MREQ") (class "Default")
      (node (ref "IC1") (pin "19") (pinfunction "MREQ_19") (pintype "output"))
      (node (ref "IC2") (pin "3") (pinfunction "(AIN0/INT2)PB2_3") (pintype "bidirectional"))
      (node (ref "IC3") (pin "22") (pinfunction "CE_22") (pintype "input"))
    )
    (net (code "63") (name "/{slash}NMI") (class "Default")
      (node (ref "IC1") (pin "17") (pinfunction "NMI_17") (pintype "input"))
      (node (ref "RN2") (pin "6") (pinfunction "6_6") (pintype "passive"))
    )
    (net (code "64") (name "/{slash}RD") (class "Default")
      (node (ref "IC1") (pin "21") (pinfunction "RD_21") (pintype "output"))
      (node (ref "IC2") (pin "21") (pinfunction "(OC2)PD7_21") (pintype "bidirectional"))
      (node (ref "IC3") (pin "24") (pinfunction "OE_24") (pintype "input"))
      (node (ref "RN2") (pin "9") (pinfunction "9_9") (pintype "passive"))
    )
    (net (code "65") (name "/{slash}RESET") (class "Default")
      (node (ref "IC1") (pin "26") (pinfunction "RESET_26") (pintype "input"))
      (node (ref "IC2") (pin "19") (pinfunction "(OC1A)PD5_19") (pintype "bidirectional"))
    )
    (net (code "66") (name "/{slash}RESUME1") (class "Default")
      (node (ref "IC2") (pin "20") (pinfunction "(ICP)PD6_20") (pintype "bidirectional"))
      (node (ref "IC8") (pin "1") (pinfunction "CLR_1") (pintype "input"))
    )
    (net (code "67") (name "/{slash}RESUME2") (class "Default")
      (node (ref "IC8") (pin "13") (pinfunction "CLR_13") (pintype "input"))
      (node (ref "R16") (pin "1") (pinfunction "1_1") (pintype "passive"))
    )
    (net (code "68") (name "/{slash}WAIT") (class "Default")
      (node (ref "IC1") (pin "24") (pinfunction "WAIT_24") (pintype "input"))
      (node (ref "IC5") (pin "11") (pinfunction "O_11") (pintype "output"))
      (node (ref "LED2") (pin "K") (pinfunction "C_K") (pintype "passive"))
    )
    (net (code "69") (name "/{slash}WR") (class "Default")
      (node (ref "IC1") (pin "22") (pinfunction "WR_22") (pintype "output"))
      (node (ref "IC2") (pin "2") (pinfunction "(T1)PB1_2") (pintype "bidirectional"))
      (node (ref "IC3") (pin "29") (pinfunction "WE_29") (pintype "input"))
    )
    (net (code "70") (name "/~{RESET}") (class "Default")
      (node (ref "C8") (pin "1") (pinfunction "1_1") (pintype "passive"))
      (node (ref "JP1") (pin "2") (pinfunction "2_2") (pintype "passive"))
      (node (ref "U1") (pin "4") (pinfunction "~{RST}_4") (pintype "input"))
      (node (ref "U2") (pin "4") (pinfunction "~{RST}_4") (pintype "input"))
    )
    (net (code "71") (name "GND") (class "Default")
      (node (ref "C1") (pin "2") (pinfunction "2_2") (pintype "passive"))
      (node (ref "C11") (pin "1") (pinfunction "1_1") (pintype "passive"))
      (node (ref "C12") (pin "1") (pinfunction "1_1") (pintype "passive"))
      (node (ref "C13") (pin "1") (pinfunction "1_1") (pintype "passive"))
      (node (ref "C14") (pin "1") (pinfunction "1_1") (pintype "passive"))
      (node (ref "C16") (pin "2") (pinfunction "2_2") (pintype "passive"))
      (node (ref "C17") (pin "1") (pinfunction "1_1") (pintype "passive"))
      (node (ref "C18") (pin "-") (pinfunction "-_-") (pintype "passive"))
      (node (ref "C2") (pin "1") (pinfunction "1_1") (pintype "passive"))
      (node (ref "C3") (pin "1") (pinfunction "1_1") (pintype "passive"))
      (node (ref "C4") (pin "-") (pinfunction "-_-") (pintype "passive"))
      (node (ref "C5") (pin "1") (pinfunction "1_1") (pintype "passive"))
      (node (ref "C6") (pin "1") (pinfunction "1_1") (pintype "passive"))
      (node (ref "C7") (pin "-") (pinfunction "-_-") (pintype "passive"))
      (node (ref "C8") (pin "2") (pinfunction "2_2") (pintype "passive"))
      (node (ref "C9") (pin "1") (pinfunction "1_1") (pintype "passive"))
      (node (ref "CON1") (pin "6") (pinfunction "6_6") (pintype "passive"))
      (node (ref "CON2") (pin "1") (pinfunction "1_1") (pintype "passive"))
      (node (ref "CON3") (pin "7") (pinfunction "7_7") (pintype "passive"))
      (node (ref "GND") (pin "1") (pinfunction "1_1") (pintype "passive"))
      (node (ref "IC1") (pin "29") (pinfunction "GND_29") (pintype "power_in"))
      (node (ref "IC2") (pin "11") (pinfunction "GND_11") (pintype "power_in"))
      (node (ref "IC2") (pin "31") (pinfunction "GND_31") (pintype "power_in"))
      (node (ref "IC3") (pin "1") (pinfunction "A18_1") (pintype "input"))
      (node (ref "IC3") (pin "16") (pinfunction "GND_16") (pintype "power_in"))
      (node (ref "IC3") (pin "2") (pinfunction "A16_2") (pintype "input"))
      (node (ref "IC4") (pin "1") (pinfunction "GND_1") (pintype "bidirectional"))
      (node (ref "IC6") (pin "1") (pinfunction "GND_1") (pintype "bidirectional"))
      (node (ref "IC7") (pin "4") (pinfunction "G2A_4") (pintype "input"))
      (node (ref "J1") (pin "GND") (pinfunction "GND_GND") (pintype "power_in"))
      (node (ref "J1") (pin "SHLD1") (pinfunction "SHIELD_SHLD1") (pintype "bidirectional"))
      (node (ref "J1") (pin "SHLD2") (pinfunction "SHIELD_SHLD2") (pintype "bidirectional"))
      (node (ref "JP1") (pin "1") (pinfunction "1_1") (pintype "passive"))
      (node (ref "KEYBOARD") (pin "3") (pinfunction "3_3") (pintype "passive"))
      (node (ref "MOD1") (pin "4") (pinfunction "GND_4") (pintype "bidirectional"))
      (node (ref "MOD1") (pin "9") (pinfunction "GND_9") (pintype "bidirectional"))
      (node (ref "MOD2") (pin "4") (pinfunction "GND_4") (pintype "bidirectional"))
      (node (ref "MOD2") (pin "9") (pinfunction "GND_9") (pintype "bidirectional"))
      (node (ref "R1") (pin "1") (pinfunction "1_1") (pintype "passive"))
      (node (ref "R6") (pin "2") (pinfunction "2_2") (pintype "passive"))
      (node (ref "RN1") (pin "1") (pinfunction "1_1") (pintype "passive"))
      (node (ref "S1") (pin "3") (pinfunction "P_3") (pintype "passive"))
      (node (ref "TP1") (pin "TP") (pinfunction "PP_TP") (pintype "input"))
      (node (ref "TP2") (pin "TP") (pinfunction "PP_TP") (pintype "input"))
      (node (ref "U1") (pin "1") (pinfunction "BOOT0_1") (pintype "input"))
      (node (ref "U1") (pin "15") (pinfunction "VSS_15") (pintype "input"))
      (node (ref "U2") (pin "1") (pinfunction "BOOT0_1") (pintype "input"))
      (node (ref "U2") (pin "15") (pinfunction "VSS_15") (pintype "input"))
      (node (ref "VGA") (pin "10") (pinfunction "10_10") (pintype "passive"))
      (node (ref "VGA") (pin "5") (pinfunction "5_5") (pintype "passive"))
      (node (ref "VGA") (pin "6") (pinfunction "6_6") (pintype "passive"))
      (node (ref "VGA") (pin "7") (pinfunction "7_7") (pintype "passive"))
      (node (ref "VGA") (pin "8") (pinfunction "8_8") (pintype "passive"))
    )
    (net (code "72") (name "Net-(CON2-Pad4)") (class "Default")
      (node (ref "CON2") (pin "4") (pinfunction "4_4") (pintype "passive"))
      (node (ref "R10") (pin "2") (pinfunction "2_2") (pintype "passive"))
    )
    (net (code "73") (name "Net-(CON2-Pad5)") (class "Default")
      (node (ref "CON2") (pin "5") (pinfunction "5_5") (pintype "passive"))
      (node (ref "R3") (pin "1") (pinfunction "1_1") (pintype "passive"))
    )
    (net (code "74") (name "Net-(IC2-AREF)") (class "Default")
      (node (ref "C1") (pin "1") (pinfunction "1_1") (pintype "passive"))
      (node (ref "IC2") (pin "32") (pinfunction "AREF_32") (pintype "passive"))
    )
    (net (code "75") (name "Net-(IC2-XTAL1)") (class "Default")
      (node (ref "C13") (pin "2") (pinfunction "2_2") (pintype "passive"))
      (node (ref "IC2") (pin "13") (pinfunction "XTAL1_13") (pintype "bidirectional"))
      (node (ref "Q1") (pin "1") (pinfunction "1_1") (pintype "passive"))
    )
    (net (code "76") (name "Net-(IC2-XTAL2)") (class "Default")
      (node (ref "C14") (pin "2") (pinfunction "2_2") (pintype "passive"))
      (node (ref "IC2") (pin "12") (pinfunction "XTAL2_12") (pintype "bidirectional"))
      (node (ref "Q1") (pin "2") (pinfunction "2_2") (pintype "passive"))
    )
    (net (code "77") (name "Net-(IC5A-O)") (class "Default")
      (node (ref "IC5") (pin "3") (pinfunction "O_3") (pintype "output"))
      (node (ref "IC8") (pin "3") (pinfunction "CLK_3") (pintype "input"))
    )
    (net (code "78") (name "Net-(IC5B-O)") (class "Default")
      (node (ref "IC5") (pin "6") (pinfunction "O_6") (pintype "output"))
      (node (ref "IC8") (pin "11") (pinfunction "CLK_11") (pintype "input"))
    )
    (net (code "79") (name "Net-(IC5C-I0)") (class "Default")
      (node (ref "IC5") (pin "9") (pinfunction "I0_9") (pintype "input"))
      (node (ref "JP2") (pin "2") (pinfunction "2_2") (pintype "passive"))
      (node (ref "R5") (pin "1") (pinfunction "1_1") (pintype "passive"))
    )
    (net (code "80") (name "Net-(IC5C-I1)") (class "Default")
      (node (ref "IC5") (pin "10") (pinfunction "I1_10") (pintype "input"))
      (node (ref "IC8") (pin "6") (pinfunction "~{Q}_6") (pintype "output"))
    )
    (net (code "81") (name "Net-(IC5C-O)") (class "Default")
      (node (ref "IC5") (pin "12") (pinfunction "I0_12") (pintype "input"))
      (node (ref "IC5") (pin "13") (pinfunction "I1_13") (pintype "input"))
      (node (ref "IC5") (pin "8") (pinfunction "O_8") (pintype "output"))
    )
    (net (code "82") (name "Net-(IC8B-~{Q})") (class "Default")
      (node (ref "IC8") (pin "8") (pinfunction "~{Q}_8") (pintype "output"))
      (node (ref "JP2") (pin "1") (pinfunction "1_1") (pintype "passive"))
    )
    (net (code "83") (name "Net-(LED1-PadA)") (class "Default")
      (node (ref "LED1") (pin "A") (pinfunction "A_A") (pintype "passive"))
      (node (ref "R9") (pin "1") (pinfunction "1_1") (pintype "passive"))
    )
    (net (code "84") (name "Net-(LED2-PadA)") (class "Default")
      (node (ref "LED2") (pin "A") (pinfunction "A_A") (pintype "passive"))
      (node (ref "R8") (pin "1") (pinfunction "1_1") (pintype "passive"))
    )
    (net (code "85") (name "Net-(MOD1-LV1)") (class "Default")
      (node (ref "CON3") (pin "2") (pinfunction "2_2") (pintype "passive"))
      (node (ref "MOD1") (pin "1") (pinfunction "LV1_1") (pintype "bidirectional"))
    )
    (net (code "86") (name "Net-(MOD1-LV2)") (class "Default")
      (node (ref "CON3") (pin "3") (pinfunction "3_3") (pintype "passive"))
      (node (ref "MOD1") (pin "2") (pinfunction "LV2_2") (pintype "bidirectional"))
    )
    (net (code "87") (name "Net-(MOD1-LV3)") (class "Default")
      (node (ref "CON3") (pin "8") (pinfunction "8_8") (pintype "passive"))
      (node (ref "MOD1") (pin "5") (pinfunction "LV3_5") (pintype "bidirectional"))
    )
    (net (code "88") (name "Net-(MOD1-LV4)") (class "Default")
      (node (ref "CON3") (pin "5") (pinfunction "5_5") (pintype "passive"))
      (node (ref "MOD1") (pin "6") (pinfunction "LV4_6") (pintype "bidirectional"))
    )
    (net (code "89") (name "Net-(MOD2-LV3)") (class "Default")
      (node (ref "MOD2") (pin "5") (pinfunction "LV3_5") (pintype "bidirectional"))
      (node (ref "U1") (pin "6") (pinfunction "PA0_6") (pintype "bidirectional"))
      (node (ref "U2") (pin "6") (pinfunction "PA0_6") (pintype "bidirectional"))
    )
    (net (code "90") (name "Net-(MOD2-LV4)") (class "Default")
      (node (ref "MOD2") (pin "6") (pinfunction "LV4_6") (pintype "bidirectional"))
      (node (ref "U1") (pin "7") (pinfunction "PA1_7") (pintype "bidirectional"))
      (node (ref "U2") (pin "7") (pinfunction "PA1_7") (pintype "bidirectional"))
    )
    (net (code "91") (name "Net-(S1-S)") (class "Default")
      (node (ref "C15") (pin "-") (pinfunction "-_-") (pintype "passive"))
      (node (ref "R2") (pin "1") (pinfunction "1_1") (pintype "passive"))
      (node (ref "S1") (pin "1") (pinfunction "S_1") (pintype "passive"))
    )
    (net (code "92") (name "Net-(T1-B)") (class "Default")
      (node (ref "C10") (pin "2") (pinfunction "2_2") (pintype "passive"))
      (node (ref "R4") (pin "2") (pinfunction "2_2") (pintype "passive"))
      (node (ref "R7") (pin "1") (pinfunction "1_1") (pintype "passive"))
      (node (ref "T1") (pin "2") (pinfunction "B_2") (pintype "passive"))
    )
    (net (code "93") (name "Net-(T1-E)") (class "Default")
      (node (ref "R12") (pin "2") (pinfunction "2_2") (pintype "passive"))
      (node (ref "R13") (pin "2") (pinfunction "2_2") (pintype "passive"))
      (node (ref "R14") (pin "2") (pinfunction "2_2") (pintype "passive"))
      (node (ref "R6") (pin "1") (pinfunction "1_1") (pintype "passive"))
      (node (ref "T1") (pin "3") (pinfunction "E_3") (pintype "passive"))
    )
    (net (code "94") (name "Net-(U1-PA2{slash}TXD)") (class "Default")
      (node (ref "U1") (pin "8") (pinfunction "PA2/TXD_8") (pintype "bidirectional"))
      (node (ref "U2") (pin "8") (pinfunction "PA2/TXD_8") (pintype "bidirectional"))
    )
    (net (code "95") (name "Net-(U1-PA3{slash}RXD)") (class "Default")
      (node (ref "U1") (pin "9") (pinfunction "PA3/RXD_9") (pintype "bidirectional"))
      (node (ref "U2") (pin "9") (pinfunction "PA3/RXD_9") (pintype "bidirectional"))
    )
    (net (code "96") (name "Net-(U1-PA4{slash}NSS)") (class "Default")
      (node (ref "U1") (pin "10") (pinfunction "PA4/NSS_10") (pintype "bidirectional"))
      (node (ref "U2") (pin "10") (pinfunction "PA4/NSS_10") (pintype "bidirectional"))
    )
    (net (code "97") (name "Net-(U1-PA5{slash}SCK)") (class "Default")
      (node (ref "R11") (pin "2") (pinfunction "2_2") (pintype "passive"))
      (node (ref "U1") (pin "11") (pinfunction "PA5/SCK_11") (pintype "bidirectional"))
      (node (ref "U2") (pin "11") (pinfunction "PA5/SCK_11") (pintype "bidirectional"))
    )
    (net (code "98") (name "Net-(U1-PA6{slash}MISO)") (class "Default")
      (node (ref "R15") (pin "2") (pinfunction "2_2") (pintype "passive"))
      (node (ref "U1") (pin "12") (pinfunction "PA6/MISO_12") (pintype "bidirectional"))
      (node (ref "U2") (pin "12") (pinfunction "PA6/MISO_12") (pintype "bidirectional"))
    )
    (net (code "99") (name "Net-(U1-PA7{slash}MOSI)") (class "Default")
      (node (ref "C10") (pin "1") (pinfunction "1_1") (pintype "passive"))
      (node (ref "R7") (pin "2") (pinfunction "2_2") (pintype "passive"))
      (node (ref "U1") (pin "13") (pinfunction "PA7/MOSI_13") (pintype "bidirectional"))
      (node (ref "U2") (pin "13") (pinfunction "PA7/MOSI_13") (pintype "bidirectional"))
    )
    (net (code "100") (name "Net-(U1-PB1)") (class "Default")
      (node (ref "U1") (pin "14") (pinfunction "PB1_14") (pintype "bidirectional"))
      (node (ref "U2") (pin "14") (pinfunction "PB1_14") (pintype "bidirectional"))
    )
    (net (code "101") (name "Net-(U1-PF0{slash}OSC_IN)") (class "Default")
      (node (ref "C6") (pin "2") (pinfunction "2_2") (pintype "passive"))
      (node (ref "Q2") (pin "1") (pinfunction "1_1") (pintype "passive"))
      (node (ref "U1") (pin "2") (pinfunction "PF0/OSC_IN_2") (pintype "input"))
      (node (ref "U2") (pin "2") (pinfunction "PF0/OSC_IN_2") (pintype "input"))
    )
    (net (code "102") (name "Net-(U1-PF1{slash}OSC_OUT)") (class "Default")
      (node (ref "C5") (pin "2") (pinfunction "2_2") (pintype "passive"))
      (node (ref "Q2") (pin "2") (pinfunction "2_2") (pintype "passive"))
      (node (ref "U1") (pin "3") (pinfunction "PF1/OSC_OUT_3") (pintype "output"))
      (node (ref "U2") (pin "3") (pinfunction "PF1/OSC_OUT_3") (pintype "output"))
    )
    (net (code "103") (name "VCC") (class "Default")
      (node (ref "C11") (pin "2") (pinfunction "2_2") (pintype "passive"))
      (node (ref "C12") (pin "2") (pinfunction "2_2") (pintype "passive"))
      (node (ref "C17") (pin "2") (pinfunction "2_2") (pintype "passive"))
      (node (ref "C4") (pin "+") (pinfunction "+_+") (pintype "passive"))
      (node (ref "C9") (pin "2") (pinfunction "2_2") (pintype "passive"))
      (node (ref "IC1") (pin "11") (pinfunction "VCC_11") (pintype "power_in"))
      (node (ref "IC2") (pin "10") (pinfunction "VCC_10") (pintype "power_in"))
      (node (ref "IC2") (pin "30") (pinfunction "AVCC_30") (pintype "power_in"))
      (node (ref "IC3") (pin "30") (pinfunction "A17_30") (pintype "input"))
      (node (ref "IC3") (pin "32") (pinfunction "VCC_32") (pintype "power_in"))
      (node (ref "IC4") (pin "2") (pinfunction "IN_2") (pintype "bidirectional"))
      (node (ref "IC6") (pin "2") (pinfunction "IN_2") (pintype "bidirectional"))
      (node (ref "IC8") (pin "10") (pinfunction "PRE_10") (pintype "input"))
      (node (ref "IC8") (pin "12") (pinfunction "D_12") (pintype "input"))
      (node (ref "IC8") (pin "2") (pinfunction "D_2") (pintype "input"))
      (node (ref "IC8") (pin "4") (pinfunction "PRE_4") (pintype "input"))
      (node (ref "J1") (pin "VBUS") (pinfunction "VBUS_VBUS") (pintype "power_in"))
      (node (ref "KEYBOARD") (pin "4") (pinfunction "4_4") (pintype "passive"))
      (node (ref "MOD1") (pin "10") (pinfunction "HV_10") (pintype "bidirectional"))
      (node (ref "MOD2") (pin "10") (pinfunction "HV_10") (pintype "bidirectional"))
      (node (ref "R16") (pin "2") (pinfunction "2_2") (pintype "passive"))
      (node (ref "R5") (pin "2") (pinfunction "2_2") (pintype "passive"))
      (node (ref "R8") (pin "2") (pinfunction "2_2") (pintype "passive"))
      (node (ref "R9") (pin "2") (pinfunction "2_2") (pintype "passive"))
      (node (ref "RN2") (pin "1") (pinfunction "1_1") (pintype "passive"))
    )
    (net (code "104") (name "unconnected-(CON1-Pad2)") (class "Default")
      (node (ref "CON1") (pin "2") (pinfunction "2_2") (pintype "passive"))
    )
    (net (code "105") (name "unconnected-(CON2-Pad2)") (class "Default")
      (node (ref "CON2") (pin "2") (pinfunction "2_2") (pintype "passive"))
    )
    (net (code "106") (name "unconnected-(CON2-Pad3)") (class "Default")
      (node (ref "CON2") (pin "3") (pinfunction "3_3") (pintype "passive"))
    )
    (net (code "107") (name "unconnected-(CON2-Pad6)") (class "Default")
      (node (ref "CON2") (pin "6") (pinfunction "6_6") (pintype "passive"))
    )
    (net (code "108") (name "unconnected-(CON3-Pad1)") (class "Default")
      (node (ref "CON3") (pin "1") (pinfunction "1_1") (pintype "passive"))
    )
    (net (code "109") (name "unconnected-(CON3-Pad4)") (class "Default")
      (node (ref "CON3") (pin "4") (pinfunction "4_4") (pintype "passive"))
    )
    (net (code "110") (name "unconnected-(CON3-Pad9)") (class "Default")
      (node (ref "CON3") (pin "9") (pinfunction "9_9") (pintype "passive"))
    )
    (net (code "111") (name "unconnected-(CON3-Pad10)") (class "Default")
      (node (ref "CON3") (pin "10") (pinfunction "10_10") (pintype "passive"))
    )
    (net (code "112") (name "unconnected-(IC1-RFSH-Pad28)") (class "Default")
      (node (ref "IC1") (pin "28") (pinfunction "RFSH_28") (pintype "output"))
    )
    (net (code "113") (name "unconnected-(IC8A-Q-Pad5)") (class "Default")
      (node (ref "IC8") (pin "5") (pinfunction "Q_5") (pintype "output"))
    )
    (net (code "114") (name "unconnected-(IC8B-Q-Pad9)") (class "Default")
      (node (ref "IC8") (pin "9") (pinfunction "Q_9") (pintype "output"))
    )
    (net (code "115") (name "unconnected-(J1-PadD+)") (class "Default")
      (node (ref "J1") (pin "D+") (pinfunction "D+_D+") (pintype "bidirectional"))
    )
    (net (code "116") (name "unconnected-(J1-PadD-)") (class "Default")
      (node (ref "J1") (pin "D-") (pinfunction "D-_D-") (pintype "bidirectional"))
    )
    (net (code "117") (name "unconnected-(KEYBOARD-Pad2)") (class "Default")
      (node (ref "KEYBOARD") (pin "2") (pinfunction "2_2") (pintype "passive"))
    )
    (net (code "118") (name "unconnected-(KEYBOARD-Pad6)") (class "Default")
      (node (ref "KEYBOARD") (pin "6") (pinfunction "6_6") (pintype "passive"))
    )
    (net (code "119") (name "unconnected-(S1-P1-Pad4)") (class "Default")
      (node (ref "S1") (pin "4") (pinfunction "P1_4") (pintype "passive"))
    )
    (net (code "120") (name "unconnected-(S1-S1-Pad2)") (class "Default")
      (node (ref "S1") (pin "2") (pinfunction "S1_2") (pintype "passive"))
    )
    (net (code "121") (name "unconnected-(VGA-Pad4)") (class "Default")
      (node (ref "VGA") (pin "4") (pinfunction "4_4") (pintype "passive"))
    )
    (net (code "122") (name "unconnected-(VGA-Pad9)") (class "Default")
      (node (ref "VGA") (pin "9") (pinfunction "9_9") (pintype "passive"))
    )
    (net (code "123") (name "unconnected-(VGA-Pad11)") (class "Default")
      (node (ref "VGA") (pin "11") (pinfunction "11_11") (pintype "passive"))
    )
    (net (code "124") (name "unconnected-(VGA-Pad12)") (class "Default")
      (node (ref "VGA") (pin "12") (pinfunction "12_12") (pintype "passive"))
    )
    (net (code "125") (name "unconnected-(VGA-Pad15)") (class "Default")
      (node (ref "VGA") (pin "15") (pinfunction "15_15") (pintype "passive"))
    )
  )
)
